# minion.net
KiCad netlist of a schematic drawn in Altium Designer
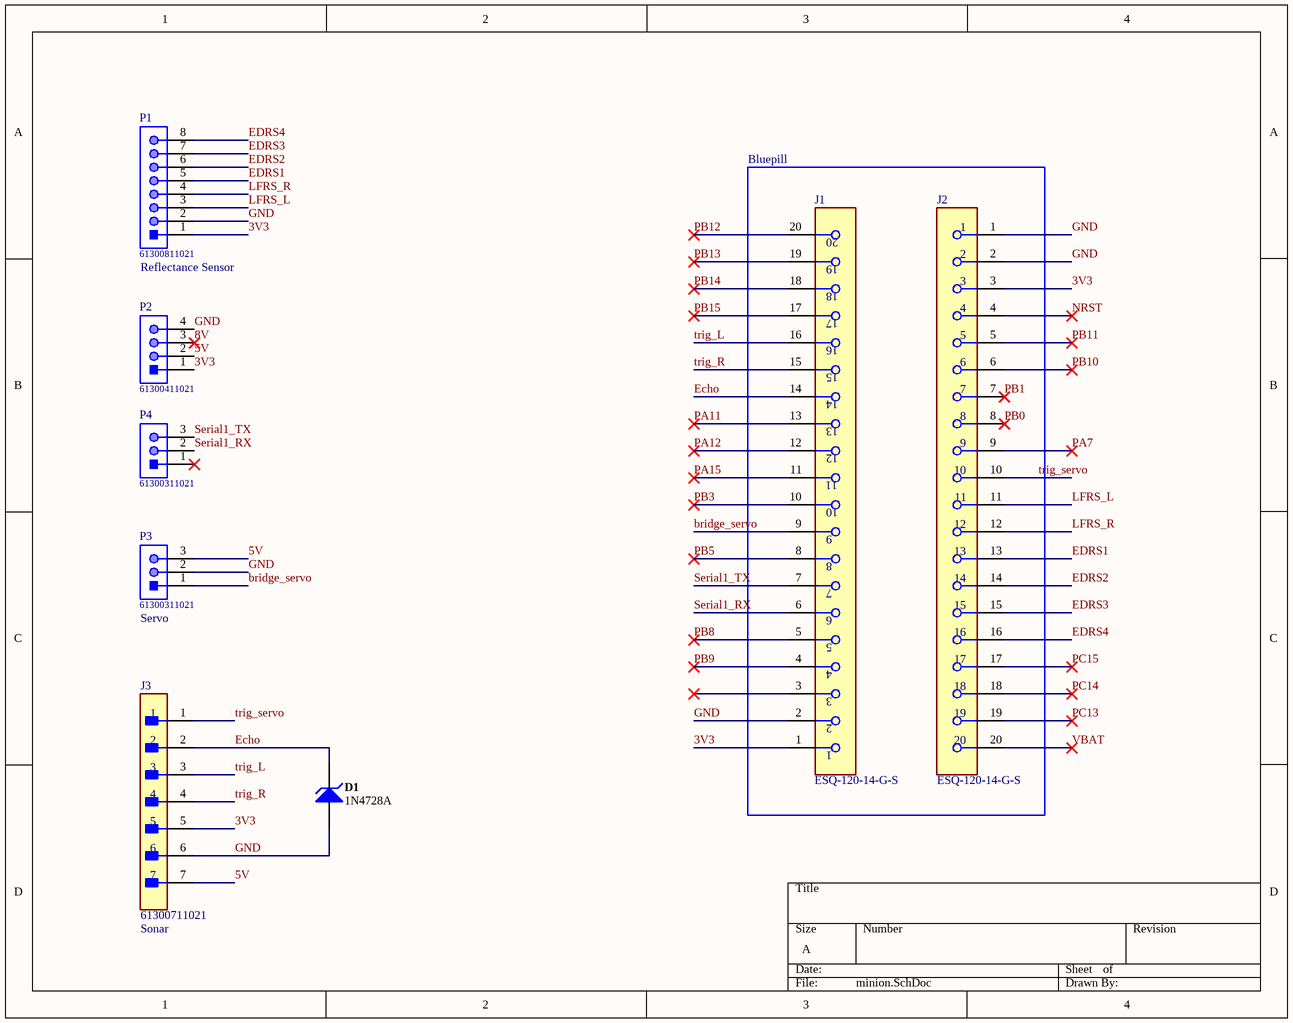
[diagram p0: minion.SchDoc]

(export (version "E")
  (design (tool "Eeschema 10.0.6"))
  (components
    (comp (ref "D1")
      (value "1N4728A")
      (footprint "FAIR-DO-41-2_V")
      (description "Zener Diode, 3.3V, 1W, 5%, -65 to 200 degC, 2-Pin DO-41, Body 2.72 x 5.2 mm, RoHS")
      (fields (field (name "MANUFACTURER") "Fairchild Semiconductor") (field (name "TOLERANCE") "5%"))
      (libsource (lib "Altium Content Vault") (part "FAIR-DZEN-A1K2-2"))
    )
    (comp (ref "J1")
      (value "ESQ-120-14-G-S")
      (footprint "FP-ESQ-120-14-G-S-MFG")
      (description "CONN SOCKET 20POS 0.1 GOLD PCB")
      (libsource (lib "Altium Content Vault") (part "dba14e038e6f7492952b7f1e871f183"))
    )
    (comp (ref "J2")
      (value "ESQ-120-14-G-S")
      (footprint "FP-ESQ-120-14-G-S-MFG")
      (description "CONN SOCKET 20POS 0.1 GOLD PCB")
      (libsource (lib "Altium Content Vault") (part "dba14e038e6f7492952b7f1e871f183"))
    )
    (comp (ref "J3")
      (value "61300711021")
      (footprint "FP-61300711021-MFG")
      (description "CONN HEADER R/A 7POS 2.54MM")
      (libsource (lib "Altium Content Vault") (part "5bcee6b94e1fee4be3f4cc3a650a442"))
    )
    (comp (ref "P1")
      (value "61300811021")
      (footprint "61300811021")
      (description "THT Angled Pin Header WR-PHD, Pitch 2.54 mm, Single Row, 8 pins")
      (fields (field (name "MANUFACTURER") "Wurth Elektronik") (field (name "PUBLISHER") "WurthElektronik"))
      (libsource (lib "Altium Content Vault") (part "WE-CN-1P-M-R8"))
    )
    (comp (ref "P2")
      (value "61300411021")
      (footprint "61300411021")
      (description "THT Angled Pin Header WR-PHD, Pitch 2.54 mm, Single Row, 4 pins")
      (fields (field (name "MANUFACTURER") "Wurth Elektronik") (field (name "PUBLISHER") "WurthElektronik"))
      (libsource (lib "Altium Content Vault") (part "WE-CN-1P-M-R4"))
    )
    (comp (ref "P3")
      (value "61300311021")
      (footprint "61300311021")
      (description "THT Angled Pin Header WR-PHD, Pitch 2.54 mm, Single Row, 3 pins")
      (fields (field (name "MANUFACTURER") "Wurth Elektronik") (field (name "PUBLISHER") "WurthElektronik"))
      (libsource (lib "Altium Content Vault") (part "WE-CN-1P-M-R3"))
    )
    (comp (ref "P4")
      (value "61300311021")
      (footprint "61300311021")
      (description "THT Angled Pin Header WR-PHD, Pitch 2.54 mm, Single Row, 3 pins")
      (fields (field (name "MANUFACTURER") "Wurth Elektronik") (field (name "PUBLISHER") "WurthElektronik"))
      (libsource (lib "Altium Content Vault") (part "WE-CN-1P-M-R3"))
    )
  )
  (nets
    (net (code "1") (name "/3V3") (class "Default")
      (node (ref "J1") (pin "1") (pinfunction "1_1") (pintype "passive"))
      (node (ref "J2") (pin "3") (pinfunction "3_3") (pintype "passive"))
      (node (ref "J3") (pin "5") (pinfunction "5_5") (pintype "passive"))
      (node (ref "P1") (pin "1") (pinfunction "1_1") (pintype "passive"))
      (node (ref "P2") (pin "1") (pinfunction "1_1") (pintype "passive"))
    )
    (net (code "2") (name "/5V") (class "Default")
      (node (ref "J3") (pin "7") (pinfunction "7_7") (pintype "passive"))
      (node (ref "P2") (pin "2") (pinfunction "2_2") (pintype "passive"))
      (node (ref "P3") (pin "3") (pinfunction "3_3") (pintype "passive"))
    )
    (net (code "3") (name "/8V") (class "Default")
      (node (ref "P2") (pin "3") (pinfunction "3_3") (pintype "passive+no_connect"))
    )
    (net (code "4") (name "/EDRS1") (class "Default")
      (node (ref "J2") (pin "13") (pinfunction "13_13") (pintype "passive"))
      (node (ref "P1") (pin "5") (pinfunction "5_5") (pintype "passive"))
    )
    (net (code "5") (name "/EDRS2") (class "Default")
      (node (ref "J2") (pin "14") (pinfunction "14_14") (pintype "passive"))
      (node (ref "P1") (pin "6") (pinfunction "6_6") (pintype "passive"))
    )
    (net (code "6") (name "/EDRS3") (class "Default")
      (node (ref "J2") (pin "15") (pinfunction "15_15") (pintype "passive"))
      (node (ref "P1") (pin "7") (pinfunction "7_7") (pintype "passive"))
    )
    (net (code "7") (name "/EDRS4") (class "Default")
      (node (ref "J2") (pin "16") (pinfunction "16_16") (pintype "passive"))
      (node (ref "P1") (pin "8") (pinfunction "8_8") (pintype "passive"))
    )
    (net (code "8") (name "/Echo") (class "Default")
      (node (ref "D1") (pin "2") (pinfunction "K_2") (pintype "passive"))
      (node (ref "J1") (pin "14") (pinfunction "14_14") (pintype "passive"))
      (node (ref "J3") (pin "2") (pinfunction "2_2") (pintype "passive"))
    )
    (net (code "9") (name "/GND") (class "Default")
      (node (ref "D1") (pin "1") (pinfunction "A_1") (pintype "passive"))
      (node (ref "J1") (pin "2") (pinfunction "2_2") (pintype "passive"))
      (node (ref "J2") (pin "1") (pinfunction "1_1") (pintype "passive"))
      (node (ref "J2") (pin "2") (pinfunction "2_2") (pintype "passive"))
      (node (ref "J3") (pin "6") (pinfunction "6_6") (pintype "passive"))
      (node (ref "P1") (pin "2") (pinfunction "2_2") (pintype "passive"))
      (node (ref "P2") (pin "4") (pinfunction "4_4") (pintype "passive"))
      (node (ref "P3") (pin "2") (pinfunction "2_2") (pintype "passive"))
    )
    (net (code "10") (name "/LFRS_L") (class "Default")
      (node (ref "J2") (pin "11") (pinfunction "11_11") (pintype "passive"))
      (node (ref "P1") (pin "3") (pinfunction "3_3") (pintype "passive"))
    )
    (net (code "11") (name "/LFRS_R") (class "Default")
      (node (ref "J2") (pin "12") (pinfunction "12_12") (pintype "passive"))
      (node (ref "P1") (pin "4") (pinfunction "4_4") (pintype "passive"))
    )
    (net (code "12") (name "/NRST") (class "Default")
      (node (ref "J2") (pin "4") (pinfunction "4_4") (pintype "passive+no_connect"))
    )
    (net (code "13") (name "/PA7") (class "Default")
      (node (ref "J2") (pin "9") (pinfunction "9_9") (pintype "passive+no_connect"))
    )
    (net (code "14") (name "/PA11") (class "Default")
      (node (ref "J1") (pin "13") (pinfunction "13_13") (pintype "passive+no_connect"))
    )
    (net (code "15") (name "/PA12") (class "Default")
      (node (ref "J1") (pin "12") (pinfunction "12_12") (pintype "passive+no_connect"))
    )
    (net (code "16") (name "/PA15") (class "Default")
      (node (ref "J1") (pin "11") (pinfunction "11_11") (pintype "passive+no_connect"))
    )
    (net (code "17") (name "/PB0") (class "Default")
      (node (ref "J2") (pin "8") (pinfunction "8_8") (pintype "passive+no_connect"))
    )
    (net (code "18") (name "/PB1") (class "Default")
      (node (ref "J2") (pin "7") (pinfunction "7_7") (pintype "passive+no_connect"))
    )
    (net (code "19") (name "/PB3") (class "Default")
      (node (ref "J1") (pin "10") (pinfunction "10_10") (pintype "passive+no_connect"))
    )
    (net (code "20") (name "/PB5") (class "Default")
      (node (ref "J1") (pin "8") (pinfunction "8_8") (pintype "passive+no_connect"))
    )
    (net (code "21") (name "/PB8") (class "Default")
      (node (ref "J1") (pin "5") (pinfunction "5_5") (pintype "passive+no_connect"))
    )
    (net (code "22") (name "/PB9") (class "Default")
      (node (ref "J1") (pin "4") (pinfunction "4_4") (pintype "passive+no_connect"))
    )
    (net (code "23") (name "/PB10") (class "Default")
      (node (ref "J2") (pin "6") (pinfunction "6_6") (pintype "passive+no_connect"))
    )
    (net (code "24") (name "/PB11") (class "Default")
      (node (ref "J2") (pin "5") (pinfunction "5_5") (pintype "passive+no_connect"))
    )
    (net (code "25") (name "/PB12") (class "Default")
      (node (ref "J1") (pin "20") (pinfunction "20_20") (pintype "passive+no_connect"))
    )
    (net (code "26") (name "/PB13") (class "Default")
      (node (ref "J1") (pin "19") (pinfunction "19_19") (pintype "passive+no_connect"))
    )
    (net (code "27") (name "/PB14") (class "Default")
      (node (ref "J1") (pin "18") (pinfunction "18_18") (pintype "passive+no_connect"))
    )
    (net (code "28") (name "/PB15") (class "Default")
      (node (ref "J1") (pin "17") (pinfunction "17_17") (pintype "passive+no_connect"))
    )
    (net (code "29") (name "/PC13") (class "Default")
      (node (ref "J2") (pin "19") (pinfunction "19_19") (pintype "passive+no_connect"))
    )
    (net (code "30") (name "/PC14") (class "Default")
      (node (ref "J2") (pin "18") (pinfunction "18_18") (pintype "passive+no_connect"))
    )
    (net (code "31") (name "/PC15") (class "Default")
      (node (ref "J2") (pin "17") (pinfunction "17_17") (pintype "passive+no_connect"))
    )
    (net (code "32") (name "/Serial1_RX") (class "Default")
      (node (ref "J1") (pin "6") (pinfunction "6_6") (pintype "passive"))
      (node (ref "P4") (pin "2") (pinfunction "2_2") (pintype "passive"))
    )
    (net (code "33") (name "/Serial1_TX") (class "Default")
      (node (ref "J1") (pin "7") (pinfunction "7_7") (pintype "passive"))
      (node (ref "P4") (pin "3") (pinfunction "3_3") (pintype "passive"))
    )
    (net (code "34") (name "/VBAT") (class "Default")
      (node (ref "J2") (pin "20") (pinfunction "20_20") (pintype "passive+no_connect"))
    )
    (net (code "35") (name "/bridge_servo") (class "Default")
      (node (ref "J1") (pin "9") (pinfunction "9_9") (pintype "passive"))
      (node (ref "P3") (pin "1") (pinfunction "1_1") (pintype "passive"))
    )
    (net (code "36") (name "/trig_L") (class "Default")
      (node (ref "J1") (pin "16") (pinfunction "16_16") (pintype "passive"))
      (node (ref "J3") (pin "3") (pinfunction "3_3") (pintype "passive"))
    )
    (net (code "37") (name "/trig_R") (class "Default")
      (node (ref "J1") (pin "15") (pinfunction "15_15") (pintype "passive"))
      (node (ref "J3") (pin "4") (pinfunction "4_4") (pintype "passive"))
    )
    (net (code "38") (name "/trig_servo") (class "Default")
      (node (ref "J2") (pin "10") (pinfunction "10_10") (pintype "passive"))
      (node (ref "J3") (pin "1") (pinfunction "1_1") (pintype "passive"))
    )
    (net (code "39") (name "unconnected-(J1-Pad3)") (class "Default")
      (node (ref "J1") (pin "3") (pinfunction "3_3") (pintype "passive+no_connect"))
    )
    (net (code "40") (name "unconnected-(P4-Pad1)") (class "Default")
      (node (ref "P4") (pin "1") (pinfunction "1_1") (pintype "passive+no_connect"))
    )
  )
)
